# FDL-3_DCP_-_v1_3.net
KiCad netlist of a schematic drawn in EAGLE
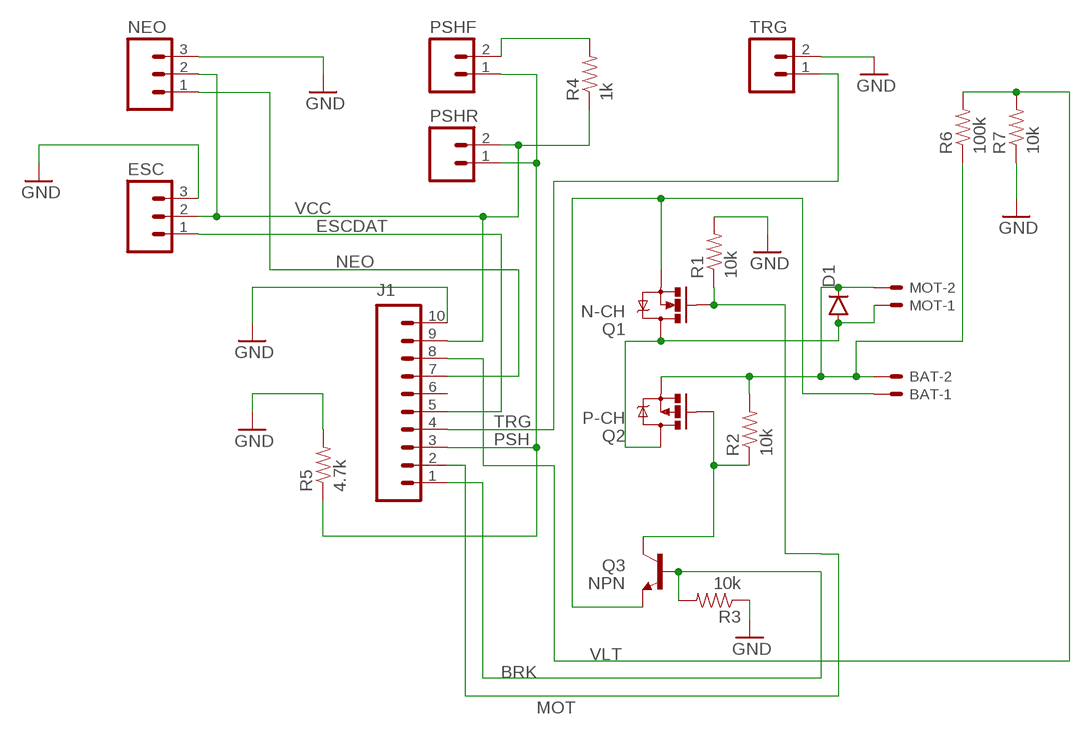
[diagram p0: schematic, sheet 1]

(export (version "E")
  (design (tool "Eeschema 10.0.6"))
  (components
    (comp (ref "BAT")
      (value "JST-XH-02-PIN-LONG-PAD")
      (footprint "eagle-import:JST-XH-02-PACKAGE-LONG-PAD")
      (libsource (lib "eagle-import") (part "JST-XH-02-PIN-LONG-PAD"))
    )
    (comp (ref "D1")
      (value "DIODEPTH")
      (footprint "eagle-import:DIODE-1N4001")
      (libsource (lib "eagle-import") (part "DIODEPTH"))
    )
    (comp (ref "ESC")
      (value "M03PTH")
      (footprint "eagle-import:1X03")
      (libsource (lib "eagle-import") (part "M03PTH"))
    )
    (comp (ref "J1")
      (value "M10SILK_FEMALE_PTH")
      (footprint "eagle-import:1X10")
      (libsource (lib "eagle-import") (part "M10SILK_FEMALE_PTH"))
    )
    (comp (ref "MOT")
      (value "JST-XH-02-PIN-LONG-PAD")
      (footprint "eagle-import:JST-XH-02-PACKAGE-LONG-PAD")
      (libsource (lib "eagle-import") (part "JST-XH-02-PIN-LONG-PAD"))
    )
    (comp (ref "NEO")
      (value "M03PTH")
      (footprint "eagle-import:1X03")
      (libsource (lib "eagle-import") (part "M03PTH"))
    )
    (comp (ref "PSHF")
      (value "M02PTH")
      (footprint "eagle-import:1X02")
      (libsource (lib "eagle-import") (part "M02PTH"))
    )
    (comp (ref "PSHR")
      (value "M02PTH")
      (footprint "eagle-import:1X02")
      (libsource (lib "eagle-import") (part "M02PTH"))
    )
    (comp (ref "Q1")
      (value "N-CH")
      (footprint "eagle-import:TO220V")
      (libsource (lib "eagle-import") (part "MOSFET-NCHANNELFQP30N06L"))
    )
    (comp (ref "Q2")
      (value "P-CH")
      (footprint "eagle-import:TO220V")
      (libsource (lib "eagle-import") (part "MOSFET-PCHANNELNDP6020P_20V_24A_LOW_VGS_TH"))
    )
    (comp (ref "Q3")
      (value "NPN")
      (footprint "eagle-import:TO-92")
      (libsource (lib "eagle-import") (part "TRANSISTOR_NPN2N3904"))
    )
    (comp (ref "R1")
      (value "10k")
      (footprint "eagle-import:AXIAL-0.3EZ")
      (libsource (lib "eagle-import") (part "10KOHM-1/4W-1%(PTH)HORIZ-KIT"))
    )
    (comp (ref "R2")
      (value "10k")
      (footprint "eagle-import:AXIAL-0.3EZ")
      (libsource (lib "eagle-import") (part "10KOHM-1/4W-1%(PTH)HORIZ-KIT"))
    )
    (comp (ref "R3")
      (value "10k")
      (footprint "eagle-import:AXIAL-0.3EZ")
      (libsource (lib "eagle-import") (part "10KOHM-1/4W-1%(PTH)HORIZ-KIT"))
    )
    (comp (ref "R4")
      (value "1k")
      (footprint "eagle-import:AXIAL-0.3EZ")
      (libsource (lib "eagle-import") (part "10KOHM-1/4W-1%(PTH)HORIZ-KIT"))
    )
    (comp (ref "R5")
      (value "4.7k")
      (footprint "eagle-import:AXIAL-0.3EZ")
      (libsource (lib "eagle-import") (part "10KOHM-1/4W-1%(PTH)HORIZ-KIT"))
    )
    (comp (ref "R6")
      (value "100k")
      (footprint "eagle-import:AXIAL-0.3EZ")
      (libsource (lib "eagle-import") (part "10KOHM-1/4W-1%(PTH)HORIZ-KIT"))
    )
    (comp (ref "R7")
      (value "10k")
      (footprint "eagle-import:AXIAL-0.3EZ")
      (libsource (lib "eagle-import") (part "10KOHM-1/4W-1%(PTH)HORIZ-KIT"))
    )
    (comp (ref "TRG")
      (value "M02PTH")
      (footprint "eagle-import:1X02")
      (libsource (lib "eagle-import") (part "M02PTH"))
    )
  )
  (nets
    (net (code "1") (name "/BRK") (class "Default")
      (node (ref "J1") (pin "1") (pinfunction "1_1") (pintype "passive"))
      (node (ref "Q3") (pin "2") (pinfunction "B_2") (pintype "passive"))
      (node (ref "R3") (pin "P$2") (pinfunction "2_P$2") (pintype "passive"))
    )
    (net (code "2") (name "/ESCDAT") (class "Default")
      (node (ref "ESC") (pin "1") (pinfunction "1_1") (pintype "passive"))
      (node (ref "J1") (pin "5") (pinfunction "5_5") (pintype "passive"))
    )
    (net (code "3") (name "/MOT") (class "Default")
      (node (ref "J1") (pin "2") (pinfunction "2_2") (pintype "passive"))
      (node (ref "Q1") (pin "1") (pinfunction "G_1") (pintype "passive"))
      (node (ref "R1") (pin "P$1") (pinfunction "1_P$1") (pintype "passive"))
    )
    (net (code "4") (name "/NEO") (class "Default")
      (node (ref "J1") (pin "7") (pinfunction "7_7") (pintype "passive"))
      (node (ref "NEO") (pin "1") (pinfunction "1_1") (pintype "passive"))
    )
    (net (code "5") (name "/PSH") (class "Default")
      (node (ref "J1") (pin "3") (pinfunction "3_3") (pintype "passive"))
      (node (ref "PSHF") (pin "1") (pinfunction "1_1") (pintype "passive"))
      (node (ref "PSHR") (pin "1") (pinfunction "1_1") (pintype "passive"))
      (node (ref "R5") (pin "P$1") (pinfunction "1_P$1") (pintype "passive"))
    )
    (net (code "6") (name "/TRG") (class "Default")
      (node (ref "J1") (pin "4") (pinfunction "4_4") (pintype "passive"))
      (node (ref "TRG") (pin "1") (pinfunction "1_1") (pintype "passive"))
    )
    (net (code "7") (name "/VCC") (class "Default")
      (node (ref "ESC") (pin "2") (pinfunction "2_2") (pintype "passive"))
      (node (ref "J1") (pin "9") (pinfunction "9_9") (pintype "passive"))
      (node (ref "NEO") (pin "2") (pinfunction "2_2") (pintype "passive"))
      (node (ref "PSHR") (pin "2") (pinfunction "2_2") (pintype "passive"))
      (node (ref "R4") (pin "P$1") (pinfunction "1_P$1") (pintype "passive"))
    )
    (net (code "8") (name "/VLT") (class "Default")
      (node (ref "J1") (pin "8") (pinfunction "8_8") (pintype "passive"))
      (node (ref "R6") (pin "P$2") (pinfunction "2_P$2") (pintype "passive"))
      (node (ref "R7") (pin "P$2") (pinfunction "2_P$2") (pintype "passive"))
    )
    (net (code "9") (name "GND") (class "Default")
      (node (ref "BAT") (pin "1") (pinfunction "S_1") (pintype "passive"))
      (node (ref "ESC") (pin "3") (pinfunction "3_3") (pintype "passive"))
      (node (ref "J1") (pin "10") (pinfunction "10_10") (pintype "passive"))
      (node (ref "NEO") (pin "3") (pinfunction "3_3") (pintype "passive"))
      (node (ref "Q1") (pin "3") (pinfunction "S_3") (pintype "passive"))
      (node (ref "Q3") (pin "1") (pinfunction "E_1") (pintype "passive"))
      (node (ref "R1") (pin "P$2") (pinfunction "2_P$2") (pintype "passive"))
      (node (ref "R3") (pin "P$1") (pinfunction "1_P$1") (pintype "passive"))
      (node (ref "R5") (pin "P$2") (pinfunction "2_P$2") (pintype "passive"))
      (node (ref "R7") (pin "P$1") (pinfunction "1_P$1") (pintype "passive"))
      (node (ref "TRG") (pin "2") (pinfunction "2_2") (pintype "passive"))
    )
    (net (code "10") (name "Net-(BATB-S)") (class "Default")
      (node (ref "BAT") (pin "2") (pinfunction "S_2") (pintype "passive"))
      (node (ref "D1") (pin "C") (pinfunction "C_C") (pintype "passive"))
      (node (ref "MOT") (pin "2") (pinfunction "S_2") (pintype "passive"))
      (node (ref "Q2") (pin "3") (pinfunction "S_3") (pintype "passive"))
      (node (ref "R2") (pin "P$2") (pinfunction "2_P$2") (pintype "passive"))
      (node (ref "R6") (pin "P$1") (pinfunction "1_P$1") (pintype "passive"))
    )
    (net (code "11") (name "Net-(MOTA-S)") (class "Default")
      (node (ref "D1") (pin "A") (pinfunction "A_A") (pintype "passive"))
      (node (ref "MOT") (pin "1") (pinfunction "S_1") (pintype "passive"))
      (node (ref "Q1") (pin "2") (pinfunction "D_2") (pintype "passive"))
      (node (ref "Q2") (pin "2") (pinfunction "D_2") (pintype "passive"))
    )
    (net (code "12") (name "Net-(Q2-G)") (class "Default")
      (node (ref "Q2") (pin "1") (pinfunction "G_1") (pintype "passive"))
      (node (ref "Q3") (pin "3") (pinfunction "C_3") (pintype "passive"))
      (node (ref "R2") (pin "P$1") (pinfunction "1_P$1") (pintype "passive"))
    )
    (net (code "13") (name "Net-(R4-2)") (class "Default")
      (node (ref "PSHF") (pin "2") (pinfunction "2_2") (pintype "passive"))
      (node (ref "R4") (pin "P$2") (pinfunction "2_P$2") (pintype "passive"))
    )
    (net (code "14") (name "unconnected-(J1-Pad6)") (class "Default")
      (node (ref "J1") (pin "6") (pinfunction "6_6") (pintype "passive"))
    )
  )
)
